# back_panel.net
KiCad netlist of a schematic drawn in EAGLE
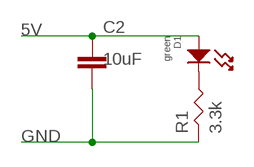
[diagram p0: schematic, sheet 1]

(export (version "E")
  (design (tool "Eeschema 10.0.6"))
  (components
    (comp (ref "C2")
      (value "10uF")
      (footprint "eagle-import:RESC0805_N")
      (libsource (lib "eagle-import") (part "CAPACITOR_0805_N"))
    )
    (comp (ref "D1")
      (value "green")
      (footprint "eagle-import:LED0805")
      (fields (field (name "HOUSEPART") "NO"))
      (libsource (lib "eagle-import") (part "LED_SINGLE-0805"))
    )
    (comp (ref "R1")
      (value "3.3k")
      (footprint "eagle-import:RES-0402")
      (libsource (lib "eagle-import") (part "RES-0402"))
    )
  )
  (nets
    (net (code "1") (name "/5V") (class "Default")
      (node (ref "C2") (pin "1") (pinfunction "1_1") (pintype "passive"))
      (node (ref "D1") (pin "ANODE") (pinfunction "ANODE_ANODE") (pintype "power_in"))
    )
    (net (code "2") (name "/GND") (class "Default")
      (node (ref "C2") (pin "2") (pinfunction "2_2") (pintype "passive"))
      (node (ref "R1") (pin "P$1") (pinfunction "P$1_P$1") (pintype "bidirectional"))
    )
    (net (code "3") (name "Net-(D1-PadCATHODE)") (class "Default")
      (node (ref "D1") (pin "CATHODE") (pinfunction "CATHODE_CATHODE") (pintype "power_in"))
      (node (ref "R1") (pin "P$2") (pinfunction "P$2_P$2") (pintype "bidirectional"))
    )
  )
)
